# Tricorder-BoosterPack.net
KiCad netlist of a schematic drawn in EAGLE
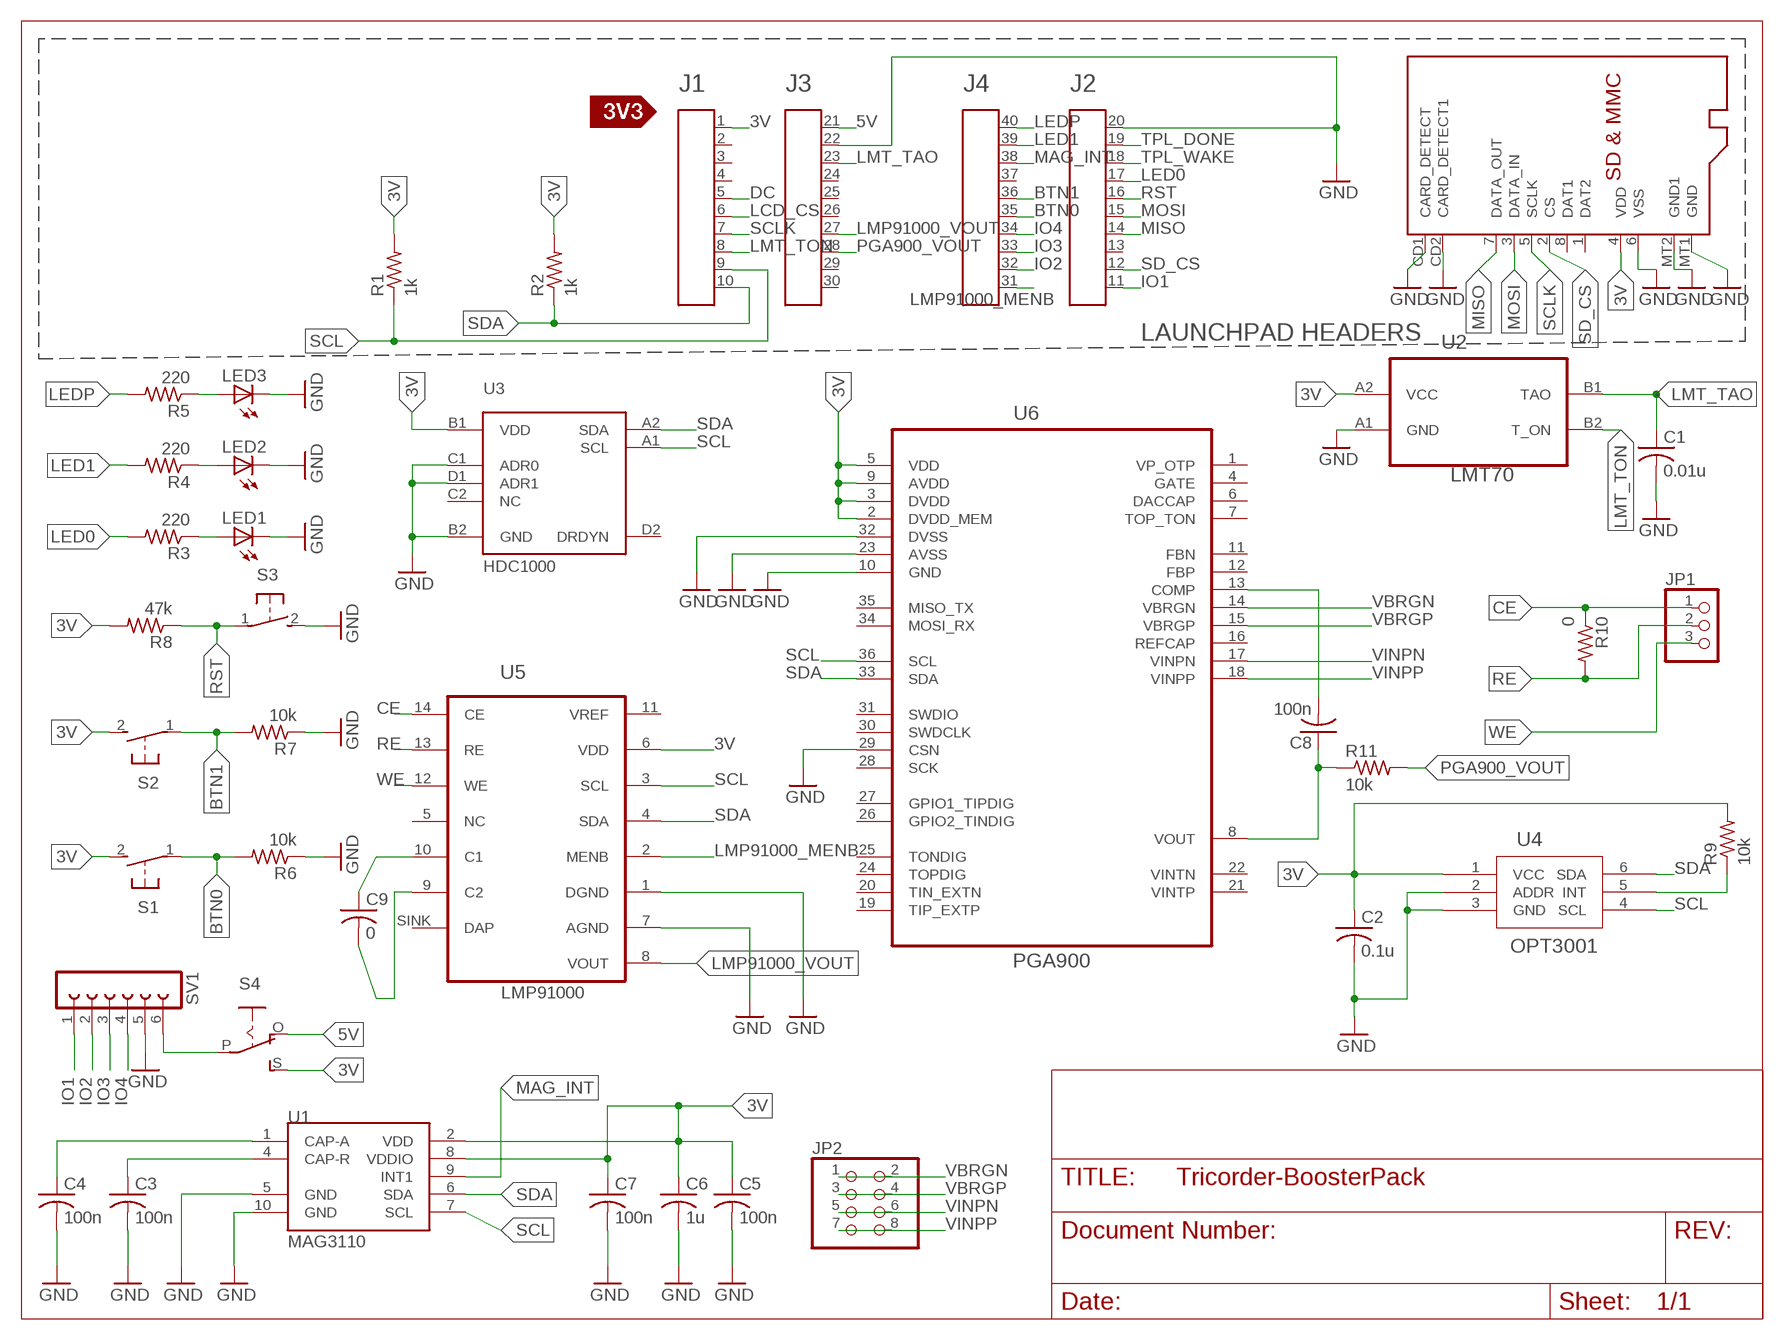
[diagram p0: schematic, sheet 1]

(export (version "E")
  (design (tool "Eeschema 10.0.6"))
  (components
    (comp (ref "A1")
      (value "HEADER4X10-BOOSTERPACK")
      (footprint "eagle-import:4X10-BOOSTERPACK")
      (libsource (lib "eagle-import") (part "HEADER4X10-BOOSTERPACK"))
    )
    (comp (ref "C1")
      (value "0.01u")
      (footprint "eagle-import:C0603")
      (libsource (lib "eagle-import") (part "C-USC0603"))
    )
    (comp (ref "C2")
      (value "0.1u")
      (footprint "eagle-import:C0603")
      (libsource (lib "eagle-import") (part "C-USC0603"))
    )
    (comp (ref "C3")
      (value "100n")
      (footprint "eagle-import:C0603")
      (libsource (lib "eagle-import") (part "C-USC0603"))
    )
    (comp (ref "C4")
      (value "100n")
      (footprint "eagle-import:C0603")
      (libsource (lib "eagle-import") (part "C-USC0603"))
    )
    (comp (ref "C5")
      (value "100n")
      (footprint "eagle-import:C0603")
      (libsource (lib "eagle-import") (part "C-USC0603"))
    )
    (comp (ref "C6")
      (value "1u")
      (footprint "eagle-import:C0603")
      (libsource (lib "eagle-import") (part "C-USC0603"))
    )
    (comp (ref "C7")
      (value "100n")
      (footprint "eagle-import:C0603")
      (libsource (lib "eagle-import") (part "C-USC0603"))
    )
    (comp (ref "C8")
      (value "100n")
      (footprint "eagle-import:C0603")
      (libsource (lib "eagle-import") (part "C-USC0603"))
    )
    (comp (ref "C9")
      (value "0")
      (footprint "eagle-import:C0603")
      (libsource (lib "eagle-import") (part "C-USC0603"))
    )
    (comp (ref "JP1")
      (value "PINHD-1X3CB")
      (footprint "eagle-import:1X03-CLEANBIG")
      (libsource (lib "eagle-import") (part "PINHD-1X3CB"))
    )
    (comp (ref "JP2")
      (value "PINHD-2X4")
      (footprint "eagle-import:2X04")
      (libsource (lib "eagle-import") (part "PINHD-2X4"))
    )
    (comp (ref "LED1")
      (value "LEDCHIPLED_0603")
      (footprint "eagle-import:CHIPLED_0603")
      (libsource (lib "eagle-import") (part "LEDCHIPLED_0603"))
    )
    (comp (ref "LED2")
      (value "LEDCHIPLED_0603")
      (footprint "eagle-import:CHIPLED_0603")
      (libsource (lib "eagle-import") (part "LEDCHIPLED_0603"))
    )
    (comp (ref "LED3")
      (value "LEDCHIPLED_0603")
      (footprint "eagle-import:CHIPLED_0603")
      (libsource (lib "eagle-import") (part "LEDCHIPLED_0603"))
    )
    (comp (ref "R1")
      (value "1k")
      (footprint "eagle-import:R0603")
      (libsource (lib "eagle-import") (part "R-US_R0603"))
    )
    (comp (ref "R2")
      (value "1k")
      (footprint "eagle-import:R0603")
      (libsource (lib "eagle-import") (part "R-US_R0603"))
    )
    (comp (ref "R3")
      (value "220")
      (footprint "eagle-import:R0603")
      (libsource (lib "eagle-import") (part "R-US_R0603"))
    )
    (comp (ref "R4")
      (value "220")
      (footprint "eagle-import:R0603")
      (libsource (lib "eagle-import") (part "R-US_R0603"))
    )
    (comp (ref "R5")
      (value "220")
      (footprint "eagle-import:R0603")
      (libsource (lib "eagle-import") (part "R-US_R0603"))
    )
    (comp (ref "R6")
      (value "10k")
      (footprint "eagle-import:R0603")
      (libsource (lib "eagle-import") (part "R-US_R0603"))
    )
    (comp (ref "R7")
      (value "10k")
      (footprint "eagle-import:R0603")
      (libsource (lib "eagle-import") (part "R-US_R0603"))
    )
    (comp (ref "R8")
      (value "47k")
      (footprint "eagle-import:R0603")
      (libsource (lib "eagle-import") (part "R-US_R0603"))
    )
    (comp (ref "R9")
      (value "10k")
      (footprint "eagle-import:R0603")
      (libsource (lib "eagle-import") (part "R-US_R0603"))
    )
    (comp (ref "R10")
      (value "0")
      (footprint "eagle-import:R0603")
      (libsource (lib "eagle-import") (part "R-US_R0603"))
    )
    (comp (ref "R11")
      (value "10k")
      (footprint "eagle-import:R0603")
      (libsource (lib "eagle-import") (part "R-US_R0603"))
    )
    (comp (ref "S1")
      (value "31-XX")
      (footprint "eagle-import:B3F-31XX")
      (libsource (lib "eagle-import") (part "31-XX"))
    )
    (comp (ref "S2")
      (value "31-XX")
      (footprint "eagle-import:B3F-31XX")
      (libsource (lib "eagle-import") (part "31-XX"))
    )
    (comp (ref "S3")
      (value "31-XX")
      (footprint "eagle-import:B3F-31XX")
      (libsource (lib "eagle-import") (part "31-XX"))
    )
    (comp (ref "S4")
      (value "EG1218S")
      (footprint "eagle-import:EG1218")
      (libsource (lib "eagle-import") (part "EG1218S"))
    )
    (comp (ref "SV1")
      (value "FE06-1")
      (footprint "eagle-import:FE06")
      (libsource (lib "eagle-import") (part "FE06-1"))
    )
    (comp (ref "U$3")
      (value "SILK_3V3_TAG")
      (footprint "eagle-import:SILK_3V3_TAG")
      (libsource (lib "eagle-import") (part "SILK_3V3_TAG"))
    )
    (comp (ref "U1")
      (value "MAG3110")
      (footprint "eagle-import:DFN-10")
      (libsource (lib "eagle-import") (part "MAG3110"))
    )
    (comp (ref "U2")
      (value "LMT70LMT70")
      (footprint "eagle-import:BGA4C40P2X2_77X77X50")
      (fields (field (name "MPN") "LMT70"))
      (libsource (lib "eagle-import") (part "LMT70LMT70"))
    )
    (comp (ref "U3")
      (value "HDC1000")
      (footprint "eagle-import:DSBGA_8_YPA")
      (libsource (lib "eagle-import") (part "HDC1000"))
    )
    (comp (ref "U4")
      (value "OPT3001")
      (footprint "eagle-import:DPK6")
      (fields
        (field (name "GENERIC_PART_NUMBER") "TPD4E001")
        (field (name "MANUFACTURER") "Texas Instruments")
        (field (name "MANUFACTURER_PART_NUMBER") "tpd4e001_dpk_6")
      )
      (libsource (lib "eagle-import") (part "OPT3001"))
    )
    (comp (ref "U5")
      (value "LMP91000")
      (footprint "eagle-import:WFDFN-14")
      (fields (field (name "DIGIKEY") "LMP91000SDE/NOPBCT-ND") (field (name "DIGIKEY_1") "LMP91000"))
      (libsource (lib "eagle-import") (part "LMP91000"))
    )
    (comp (ref "U6")
      (value "PGA900")
      (footprint "eagle-import:QFN50P600X600X90-37N")
      (libsource (lib "eagle-import") (part "PGA900"))
    )
    (comp (ref "U7")
      (value "MICROSD")
      (footprint "eagle-import:MICROSD")
      (libsource (lib "eagle-import") (part "MICROSD"))
    )
  )
  (nets
    (net (code "1") (name "/DC") (class "Default")
      (node (ref "A1") (pin "5") (pinfunction "P$5_5") (pintype "bidirectional"))
    )
    (net (code "2") (name "/IO1") (class "Default")
      (node (ref "A1") (pin "11") (pinfunction "P$11_11") (pintype "bidirectional"))
      (node (ref "SV1") (pin "1") (pinfunction "1_1") (pintype "passive"))
    )
    (net (code "3") (name "/IO2") (class "Default")
      (node (ref "A1") (pin "32") (pinfunction "P$32_32") (pintype "bidirectional"))
      (node (ref "SV1") (pin "2") (pinfunction "2_2") (pintype "passive"))
    )
    (net (code "4") (name "/IO3") (class "Default")
      (node (ref "A1") (pin "33") (pinfunction "P$33_33") (pintype "bidirectional"))
      (node (ref "SV1") (pin "3") (pinfunction "3_3") (pintype "passive"))
    )
    (net (code "5") (name "/IO4") (class "Default")
      (node (ref "A1") (pin "34") (pinfunction "P$34_34") (pintype "bidirectional"))
      (node (ref "SV1") (pin "4") (pinfunction "4_4") (pintype "passive"))
    )
    (net (code "6") (name "/LCD_CS") (class "Default")
      (node (ref "A1") (pin "6") (pinfunction "P$6_6") (pintype "bidirectional"))
    )
    (net (code "7") (name "/LMP91000_MENB") (class "Default")
      (node (ref "A1") (pin "31") (pinfunction "P$31_31") (pintype "bidirectional"))
      (node (ref "U5") (pin "2") (pinfunction "MENB_2") (pintype "passive"))
    )
    (net (code "8") (name "/TPL_DONE") (class "Default")
      (node (ref "A1") (pin "19") (pinfunction "P$19_19") (pintype "bidirectional"))
    )
    (net (code "9") (name "/TPL_WAKE") (class "Default")
      (node (ref "A1") (pin "18") (pinfunction "P$18_18") (pintype "bidirectional"))
    )
    (net (code "10") (name "/VBRGN") (class "Default")
      (node (ref "JP2") (pin "1") (pinfunction "1_1") (pintype "passive"))
      (node (ref "JP2") (pin "2") (pinfunction "2_2") (pintype "passive"))
      (node (ref "U6") (pin "14") (pinfunction "VBRGN_14") (pintype "bidirectional"))
    )
    (net (code "11") (name "/VBRGP") (class "Default")
      (node (ref "JP2") (pin "3") (pinfunction "3_3") (pintype "passive"))
      (node (ref "JP2") (pin "4") (pinfunction "4_4") (pintype "passive"))
      (node (ref "U6") (pin "15") (pinfunction "VBRGP_15") (pintype "bidirectional"))
    )
    (net (code "12") (name "/VINPN") (class "Default")
      (node (ref "JP2") (pin "5") (pinfunction "5_5") (pintype "passive"))
      (node (ref "JP2") (pin "6") (pinfunction "6_6") (pintype "passive"))
      (node (ref "U6") (pin "17") (pinfunction "VINPN_17") (pintype "bidirectional"))
    )
    (net (code "13") (name "/VINPP") (class "Default")
      (node (ref "JP2") (pin "7") (pinfunction "7_7") (pintype "passive"))
      (node (ref "JP2") (pin "8") (pinfunction "8_8") (pintype "passive"))
      (node (ref "U6") (pin "18") (pinfunction "VINPP_18") (pintype "bidirectional"))
    )
    (net (code "14") (name "/VREF") (class "Default")
      (node (ref "U5") (pin "11") (pinfunction "VREF_11") (pintype "power_in"))
    )
    (net (code "15") (name "3V") (class "Default")
      (node (ref "A1") (pin "1") (pinfunction "P$1_1") (pintype "bidirectional"))
      (node (ref "C2") (pin "1") (pinfunction "1_1") (pintype "passive"))
      (node (ref "C5") (pin "1") (pinfunction "1_1") (pintype "passive"))
      (node (ref "C6") (pin "1") (pinfunction "1_1") (pintype "passive"))
      (node (ref "C7") (pin "1") (pinfunction "1_1") (pintype "passive"))
      (node (ref "R1") (pin "2") (pinfunction "2_2") (pintype "passive"))
      (node (ref "R2") (pin "2") (pinfunction "2_2") (pintype "passive"))
      (node (ref "R8") (pin "2") (pinfunction "2_2") (pintype "passive"))
      (node (ref "R9") (pin "2") (pinfunction "2_2") (pintype "passive"))
      (node (ref "S1") (pin "2") (pinfunction "S_2") (pintype "passive"))
      (node (ref "S2") (pin "2") (pinfunction "S_2") (pintype "passive"))
      (node (ref "S4") (pin "S") (pinfunction "S_S") (pintype "passive"))
      (node (ref "U1") (pin "2") (pinfunction "VDD_2") (pintype "bidirectional"))
      (node (ref "U1") (pin "8") (pinfunction "VDDIO_8") (pintype "bidirectional"))
      (node (ref "U2") (pin "A2") (pinfunction "VCC_A2") (pintype "power_in"))
      (node (ref "U3") (pin "B1") (pinfunction "VDD_B1") (pintype "power_in"))
      (node (ref "U4") (pin "1") (pinfunction "VCC_1") (pintype "power_in"))
      (node (ref "U5") (pin "6") (pinfunction "VDD_6") (pintype "power_in"))
      (node (ref "U6") (pin "2") (pinfunction "DVDD_MEM_2") (pintype "power_in"))
      (node (ref "U6") (pin "3") (pinfunction "DVDD_3") (pintype "power_in"))
      (node (ref "U6") (pin "5") (pinfunction "VDD_5") (pintype "power_in"))
      (node (ref "U6") (pin "9") (pinfunction "AVDD_9") (pintype "power_in"))
      (node (ref "U7") (pin "4") (pinfunction "VDD_4") (pintype "power_in"))
    )
    (net (code "16") (name "5V") (class "Default")
      (node (ref "A1") (pin "21") (pinfunction "P$21_21") (pintype "bidirectional"))
      (node (ref "S4") (pin "O") (pinfunction "O_O") (pintype "passive"))
    )
    (net (code "17") (name "BTN0") (class "Default")
      (node (ref "A1") (pin "35") (pinfunction "P$35_35") (pintype "bidirectional"))
      (node (ref "R6") (pin "2") (pinfunction "2_2") (pintype "passive"))
      (node (ref "S1") (pin "1") (pinfunction "P_1") (pintype "passive"))
    )
    (net (code "18") (name "BTN1") (class "Default")
      (node (ref "A1") (pin "36") (pinfunction "P$36_36") (pintype "bidirectional"))
      (node (ref "R7") (pin "2") (pinfunction "2_2") (pintype "passive"))
      (node (ref "S2") (pin "1") (pinfunction "P_1") (pintype "passive"))
    )
    (net (code "19") (name "CE") (class "Default")
      (node (ref "JP1") (pin "1") (pinfunction "1_1") (pintype "passive"))
      (node (ref "R10") (pin "1") (pinfunction "1_1") (pintype "passive"))
      (node (ref "U5") (pin "14") (pinfunction "CE_14") (pintype "bidirectional"))
    )
    (net (code "20") (name "GND") (class "Default")
      (node (ref "A1") (pin "20") (pinfunction "P$20_20") (pintype "bidirectional"))
      (node (ref "A1") (pin "22") (pinfunction "P$22_22") (pintype "bidirectional"))
      (node (ref "C1") (pin "2") (pinfunction "2_2") (pintype "passive"))
      (node (ref "C2") (pin "2") (pinfunction "2_2") (pintype "passive"))
      (node (ref "C3") (pin "2") (pinfunction "2_2") (pintype "passive"))
      (node (ref "C4") (pin "2") (pinfunction "2_2") (pintype "passive"))
      (node (ref "C5") (pin "2") (pinfunction "2_2") (pintype "passive"))
      (node (ref "C6") (pin "2") (pinfunction "2_2") (pintype "passive"))
      (node (ref "C7") (pin "2") (pinfunction "2_2") (pintype "passive"))
      (node (ref "LED1") (pin "C") (pinfunction "C_C") (pintype "passive"))
      (node (ref "LED2") (pin "C") (pinfunction "C_C") (pintype "passive"))
      (node (ref "LED3") (pin "C") (pinfunction "C_C") (pintype "passive"))
      (node (ref "R6") (pin "1") (pinfunction "1_1") (pintype "passive"))
      (node (ref "R7") (pin "1") (pinfunction "1_1") (pintype "passive"))
      (node (ref "S3") (pin "2") (pinfunction "S_2") (pintype "passive"))
      (node (ref "SV1") (pin "5") (pinfunction "5_5") (pintype "passive"))
      (node (ref "U1") (pin "10") (pinfunction "GND_10") (pintype "bidirectional"))
      (node (ref "U1") (pin "5") (pinfunction "GND_5") (pintype "bidirectional"))
      (node (ref "U2") (pin "A1") (pinfunction "GND_A1") (pintype "passive"))
      (node (ref "U3") (pin "B2") (pinfunction "GND_B2") (pintype "power_in"))
      (node (ref "U3") (pin "C1") (pinfunction "ADR0_C1") (pintype "input"))
      (node (ref "U3") (pin "D1") (pinfunction "ADR1_D1") (pintype "input"))
      (node (ref "U4") (pin "2") (pinfunction "ADDR_2") (pintype "passive"))
      (node (ref "U4") (pin "3") (pinfunction "GND_3") (pintype "power_in"))
      (node (ref "U5") (pin "1") (pinfunction "DGND_1") (pintype "passive"))
      (node (ref "U5") (pin "7") (pinfunction "AGND_7") (pintype "passive"))
      (node (ref "U6") (pin "10") (pinfunction "GND_10") (pintype "power_in"))
      (node (ref "U6") (pin "23") (pinfunction "AVSS_23") (pintype "power_in"))
      (node (ref "U6") (pin "29") (pinfunction "CSN_29") (pintype "output"))
      (node (ref "U6") (pin "32") (pinfunction "DVSS_32") (pintype "power_in"))
      (node (ref "U7") (pin "6") (pinfunction "VSS_6") (pintype "power_in"))
      (node (ref "U7") (pin "CD1") (pinfunction "CARD_DETECT_CD1") (pintype "passive"))
      (node (ref "U7") (pin "CD2") (pinfunction "CARD_DETECT1_CD2") (pintype "passive"))
      (node (ref "U7") (pin "MT1") (pinfunction "GND_MT1") (pintype "power_in"))
      (node (ref "U7") (pin "MT2") (pinfunction "GND1_MT2") (pintype "power_in"))
    )
    (net (code "21") (name "LED0") (class "Default")
      (node (ref "A1") (pin "17") (pinfunction "P$17_17") (pintype "bidirectional"))
      (node (ref "R3") (pin "2") (pinfunction "2_2") (pintype "passive"))
    )
    (net (code "22") (name "LED1") (class "Default")
      (node (ref "A1") (pin "39") (pinfunction "P$39_39") (pintype "bidirectional"))
      (node (ref "R4") (pin "2") (pinfunction "2_2") (pintype "passive"))
    )
    (net (code "23") (name "LEDP") (class "Default")
      (node (ref "A1") (pin "40") (pinfunction "P$40_40") (pintype "bidirectional"))
      (node (ref "R5") (pin "2") (pinfunction "2_2") (pintype "passive"))
    )
    (net (code "24") (name "LMP91000_VOUT") (class "Default")
      (node (ref "A1") (pin "27") (pinfunction "P$27_27") (pintype "bidirectional"))
      (node (ref "U5") (pin "8") (pinfunction "VOUT_8") (pintype "passive"))
    )
    (net (code "25") (name "LMT_TAO") (class "Default")
      (node (ref "A1") (pin "23") (pinfunction "P$23_23") (pintype "bidirectional"))
      (node (ref "C1") (pin "1") (pinfunction "1_1") (pintype "passive"))
      (node (ref "U2") (pin "B1") (pinfunction "TAO_B1") (pintype "output"))
    )
    (net (code "26") (name "LMT_TON") (class "Default")
      (node (ref "A1") (pin "8") (pinfunction "P$8_8") (pintype "bidirectional"))
      (node (ref "U2") (pin "B2") (pinfunction "T_ON_B2") (pintype "input"))
    )
    (net (code "27") (name "MAG_INT") (class "Default")
      (node (ref "A1") (pin "38") (pinfunction "P$38_38") (pintype "bidirectional"))
      (node (ref "U1") (pin "9") (pinfunction "INT1_9") (pintype "bidirectional"))
    )
    (net (code "28") (name "MISO") (class "Default")
      (node (ref "A1") (pin "14") (pinfunction "P$14_14") (pintype "bidirectional"))
      (node (ref "U7") (pin "7") (pinfunction "DATA_OUT_7") (pintype "output"))
    )
    (net (code "29") (name "MOSI") (class "Default")
      (node (ref "A1") (pin "15") (pinfunction "P$15_15") (pintype "bidirectional"))
      (node (ref "U7") (pin "3") (pinfunction "DATA_IN_3") (pintype "input"))
    )
    (net (code "30") (name "Net-(LED1-PadA)") (class "Default")
      (node (ref "LED1") (pin "A") (pinfunction "A_A") (pintype "passive"))
      (node (ref "R3") (pin "1") (pinfunction "1_1") (pintype "passive"))
    )
    (net (code "31") (name "Net-(LED2-PadA)") (class "Default")
      (node (ref "LED2") (pin "A") (pinfunction "A_A") (pintype "passive"))
      (node (ref "R4") (pin "1") (pinfunction "1_1") (pintype "passive"))
    )
    (net (code "32") (name "Net-(LED3-PadA)") (class "Default")
      (node (ref "LED3") (pin "A") (pinfunction "A_A") (pintype "passive"))
      (node (ref "R5") (pin "1") (pinfunction "1_1") (pintype "passive"))
    )
    (net (code "33") (name "Net-(S4-PadP)") (class "Default")
      (node (ref "S4") (pin "P") (pinfunction "P_P") (pintype "passive"))
      (node (ref "SV1") (pin "6") (pinfunction "6_6") (pintype "passive"))
    )
    (net (code "34") (name "Net-(U1-CAP-A)") (class "Default")
      (node (ref "C4") (pin "1") (pinfunction "1_1") (pintype "passive"))
      (node (ref "U1") (pin "1") (pinfunction "CAP-A_1") (pintype "bidirectional"))
    )
    (net (code "35") (name "Net-(U1-CAP-R)") (class "Default")
      (node (ref "C3") (pin "1") (pinfunction "1_1") (pintype "passive"))
      (node (ref "U1") (pin "4") (pinfunction "CAP-R_4") (pintype "bidirectional"))
    )
    (net (code "36") (name "Net-(U4-INT)") (class "Default")
      (node (ref "R9") (pin "1") (pinfunction "1_1") (pintype "passive"))
      (node (ref "U4") (pin "5") (pinfunction "INT_5") (pintype "bidirectional"))
    )
    (net (code "37") (name "Net-(U5-C1)") (class "Default")
      (node (ref "C9") (pin "1") (pinfunction "1_1") (pintype "passive"))
      (node (ref "U5") (pin "10") (pinfunction "C1_10") (pintype "passive"))
    )
    (net (code "38") (name "Net-(U5-C2)") (class "Default")
      (node (ref "C9") (pin "2") (pinfunction "2_2") (pintype "passive"))
      (node (ref "U5") (pin "9") (pinfunction "C2_9") (pintype "passive"))
    )
    (net (code "39") (name "Net-(U6-COMP)") (class "Default")
      (node (ref "C8") (pin "2") (pinfunction "2_2") (pintype "passive"))
      (node (ref "U6") (pin "13") (pinfunction "COMP_13") (pintype "bidirectional"))
    )
    (net (code "40") (name "Net-(U6-VOUT)") (class "Default")
      (node (ref "C8") (pin "1") (pinfunction "1_1") (pintype "passive"))
      (node (ref "R11") (pin "1") (pinfunction "1_1") (pintype "passive"))
      (node (ref "U6") (pin "8") (pinfunction "VOUT_8") (pintype "bidirectional"))
    )
    (net (code "41") (name "PGA900_VOUT") (class "Default")
      (node (ref "A1") (pin "28") (pinfunction "P$28_28") (pintype "bidirectional"))
      (node (ref "R11") (pin "2") (pinfunction "2_2") (pintype "passive"))
    )
    (net (code "42") (name "RE") (class "Default")
      (node (ref "JP1") (pin "2") (pinfunction "2_2") (pintype "passive"))
      (node (ref "R10") (pin "2") (pinfunction "2_2") (pintype "passive"))
      (node (ref "U5") (pin "13") (pinfunction "RE_13") (pintype "bidirectional"))
    )
    (net (code "43") (name "RST") (class "Default")
      (node (ref "A1") (pin "16") (pinfunction "P$16_16") (pintype "bidirectional"))
      (node (ref "R8") (pin "1") (pinfunction "1_1") (pintype "passive"))
      (node (ref "S3") (pin "1") (pinfunction "P_1") (pintype "passive"))
    )
    (net (code "44") (name "SCL") (class "Default")
      (node (ref "A1") (pin "9") (pinfunction "P$9_9") (pintype "bidirectional"))
      (node (ref "R1") (pin "1") (pinfunction "1_1") (pintype "passive"))
      (node (ref "U1") (pin "7") (pinfunction "SCL_7") (pintype "bidirectional"))
      (node (ref "U3") (pin "A1") (pinfunction "SCL_A1") (pintype "input"))
      (node (ref "U4") (pin "4") (pinfunction "SCL_4") (pintype "input"))
      (node (ref "U5") (pin "3") (pinfunction "SCL_3") (pintype "bidirectional"))
      (node (ref "U6") (pin "36") (pinfunction "SCL_36") (pintype "bidirectional"))
    )
    (net (code "45") (name "SCLK") (class "Default")
      (node (ref "A1") (pin "7") (pinfunction "P$7_7") (pintype "bidirectional"))
      (node (ref "U7") (pin "5") (pinfunction "SCLK_5") (pintype "input"))
    )
    (net (code "46") (name "SDA") (class "Default")
      (node (ref "A1") (pin "10") (pinfunction "P$10_10") (pintype "bidirectional"))
      (node (ref "R2") (pin "1") (pinfunction "1_1") (pintype "passive"))
      (node (ref "U1") (pin "6") (pinfunction "SDA_6") (pintype "bidirectional"))
      (node (ref "U3") (pin "A2") (pinfunction "SDA_A2") (pintype "bidirectional"))
      (node (ref "U4") (pin "6") (pinfunction "SDA_6") (pintype "bidirectional"))
      (node (ref "U5") (pin "4") (pinfunction "SDA_4") (pintype "passive"))
      (node (ref "U6") (pin "33") (pinfunction "SDA_33") (pintype "bidirectional"))
    )
    (net (code "47") (name "SD_CS") (class "Default")
      (node (ref "A1") (pin "12") (pinfunction "P$12_12") (pintype "bidirectional"))
      (node (ref "U7") (pin "2") (pinfunction "CS_2") (pintype "input"))
    )
    (net (code "48") (name "WE") (class "Default")
      (node (ref "JP1") (pin "3") (pinfunction "3_3") (pintype "passive"))
      (node (ref "U5") (pin "12") (pinfunction "WE_12") (pintype "bidirectional"))
    )
    (net (code "49") (name "unconnected-(A1-P$2-Pad2)") (class "Default")
      (node (ref "A1") (pin "2") (pinfunction "P$2_2") (pintype "bidirectional"))
    )
    (net (code "50") (name "unconnected-(A1-P$3-Pad3)") (class "Default")
      (node (ref "A1") (pin "3") (pinfunction "P$3_3") (pintype "bidirectional"))
    )
    (net (code "51") (name "unconnected-(A1-P$4-Pad4)") (class "Default")
      (node (ref "A1") (pin "4") (pinfunction "P$4_4") (pintype "bidirectional"))
    )
    (net (code "52") (name "unconnected-(A1-P$13-Pad13)") (class "Default")
      (node (ref "A1") (pin "13") (pinfunction "P$13_13") (pintype "bidirectional"))
    )
    (net (code "53") (name "unconnected-(A1-P$24-Pad24)") (class "Default")
      (node (ref "A1") (pin "24") (pinfunction "P$24_24") (pintype "bidirectional"))
    )
    (net (code "54") (name "unconnected-(A1-P$25-Pad25)") (class "Default")
      (node (ref "A1") (pin "25") (pinfunction "P$25_25") (pintype "bidirectional"))
    )
    (net (code "55") (name "unconnected-(A1-P$26-Pad26)") (class "Default")
      (node (ref "A1") (pin "26") (pinfunction "P$26_26") (pintype "bidirectional"))
    )
    (net (code "56") (name "unconnected-(A1-P$29-Pad29)") (class "Default")
      (node (ref "A1") (pin "29") (pinfunction "P$29_29") (pintype "bidirectional"))
    )
    (net (code "57") (name "unconnected-(A1-P$30-Pad30)") (class "Default")
      (node (ref "A1") (pin "30") (pinfunction "P$30_30") (pintype "bidirectional"))
    )
    (net (code "58") (name "unconnected-(A1-P$37-Pad37)") (class "Default")
      (node (ref "A1") (pin "37") (pinfunction "P$37_37") (pintype "bidirectional"))
    )
    (net (code "59") (name "unconnected-(U3-DRDYN-PadD2)") (class "Default")
      (node (ref "U3") (pin "D2") (pinfunction "DRDYN_D2") (pintype "output"))
    )
    (net (code "60") (name "unconnected-(U3-NC-PadC2)") (class "Default")
      (node (ref "U3") (pin "C2") (pinfunction "NC_C2") (pintype "no_connect"))
    )
    (net (code "61") (name "unconnected-(U5-DAP-PadSINK)") (class "Default")
      (node (ref "U5") (pin "SINK") (pinfunction "DAP_SINK") (pintype "passive"))
    )
    (net (code "62") (name "unconnected-(U5-NC-Pad5)") (class "Default")
      (node (ref "U5") (pin "5") (pinfunction "NC_5") (pintype "passive"))
    )
    (net (code "63") (name "unconnected-(U6-DACCAP-Pad6)") (class "Default")
      (node (ref "U6") (pin "6") (pinfunction "DACCAP_6") (pintype "bidirectional"))
    )
    (net (code "64") (name "unconnected-(U6-FBN-Pad11)") (class "Default")
      (node (ref "U6") (pin "11") (pinfunction "FBN_11") (pintype "bidirectional"))
    )
    (net (code "65") (name "unconnected-(U6-FBP-Pad12)") (class "Default")
      (node (ref "U6") (pin "12") (pinfunction "FBP_12") (pintype "bidirectional"))
    )
    (net (code "66") (name "unconnected-(U6-GATE-Pad4)") (class "Default")
      (node (ref "U6") (pin "4") (pinfunction "GATE_4") (pintype "bidirectional"))
    )
    (net (code "67") (name "unconnected-(U6-GPIO1_TIPDIG-Pad27)") (class "Default")
      (node (ref "U6") (pin "27") (pinfunction "GPIO1_TIPDIG_27") (pintype "bidirectional"))
    )
    (net (code "68") (name "unconnected-(U6-GPIO2_TINDIG-Pad26)") (class "Default")
      (node (ref "U6") (pin "26") (pinfunction "GPIO2_TINDIG_26") (pintype "bidirectional"))
    )
    (net (code "69") (name "unconnected-(U6-MISO_TX-Pad35)") (class "Default")
      (node (ref "U6") (pin "35") (pinfunction "MISO_TX_35") (pintype "output"))
    )
    (net (code "70") (name "unconnected-(U6-MOSI_RX-Pad34)") (class "Default")
      (node (ref "U6") (pin "34") (pinfunction "MOSI_RX_34") (pintype "input"))
    )
    (net (code "71") (name "unconnected-(U6-REFCAP-Pad16)") (class "Default")
      (node (ref "U6") (pin "16") (pinfunction "REFCAP_16") (pintype "bidirectional"))
    )
    (net (code "72") (name "unconnected-(U6-SCK-Pad28)") (class "Default")
      (node (ref "U6") (pin "28") (pinfunction "SCK_28") (pintype "output"))
    )
    (net (code "73") (name "unconnected-(U6-SWDCLK-Pad30)") (class "Default")
      (node (ref "U6") (pin "30") (pinfunction "SWDCLK_30") (pintype "bidirectional"))
    )
    (net (code "74") (name "unconnected-(U6-SWDIO-Pad31)") (class "Default")
      (node (ref "U6") (pin "31") (pinfunction "SWDIO_31") (pintype "bidirectional"))
    )
    (net (code "75") (name "unconnected-(U6-TIN_EXTN-Pad20)") (class "Default")
      (node (ref "U6") (pin "20") (pinfunction "TIN_EXTN_20") (pintype "input"))
    )
    (net (code "76") (name "unconnected-(U6-TIP_EXTP-Pad19)") (class "Default")
      (node (ref "U6") (pin "19") (pinfunction "TIP_EXTP_19") (pintype "input"))
    )
    (net (code "77") (name "unconnected-(U6-TONDIG-Pad25)") (class "Default")
      (node (ref "U6") (pin "25") (pinfunction "TONDIG_25") (pintype "output"))
    )
    (net (code "78") (name "unconnected-(U6-TOPDIG-Pad24)") (class "Default")
      (node (ref "U6") (pin "24") (pinfunction "TOPDIG_24") (pintype "output"))
    )
    (net (code "79") (name "unconnected-(U6-TOP_TON-Pad7)") (class "Default")
      (node (ref "U6") (pin "7") (pinfunction "TOP_TON_7") (pintype "bidirectional"))
    )
    (net (code "80") (name "unconnected-(U6-VINTN-Pad22)") (class "Default")
      (node (ref "U6") (pin "22") (pinfunction "VINTN_22") (pintype "input"))
    )
    (net (code "81") (name "unconnected-(U6-VINTP-Pad21)") (class "Default")
      (node (ref "U6") (pin "21") (pinfunction "VINTP_21") (pintype "bidirectional"))
    )
    (net (code "82") (name "unconnected-(U6-VP_OTP-Pad1)") (class "Default")
      (node (ref "U6") (pin "1") (pinfunction "VP_OTP_1") (pintype "bidirectional"))
    )
    (net (code "83") (name "unconnected-(U7-DAT1-Pad8)") (class "Default")
      (node (ref "U7") (pin "8") (pinfunction "DAT1_8") (pintype "bidirectional"))
    )
    (net (code "84") (name "unconnected-(U7-DAT2-Pad1)") (class "Default")
      (node (ref "U7") (pin "1") (pinfunction "DAT2_1") (pintype "bidirectional"))
    )
  )
)
